# LSM6DS3_Breakout.net
KiCad netlist of a schematic drawn in EAGLE
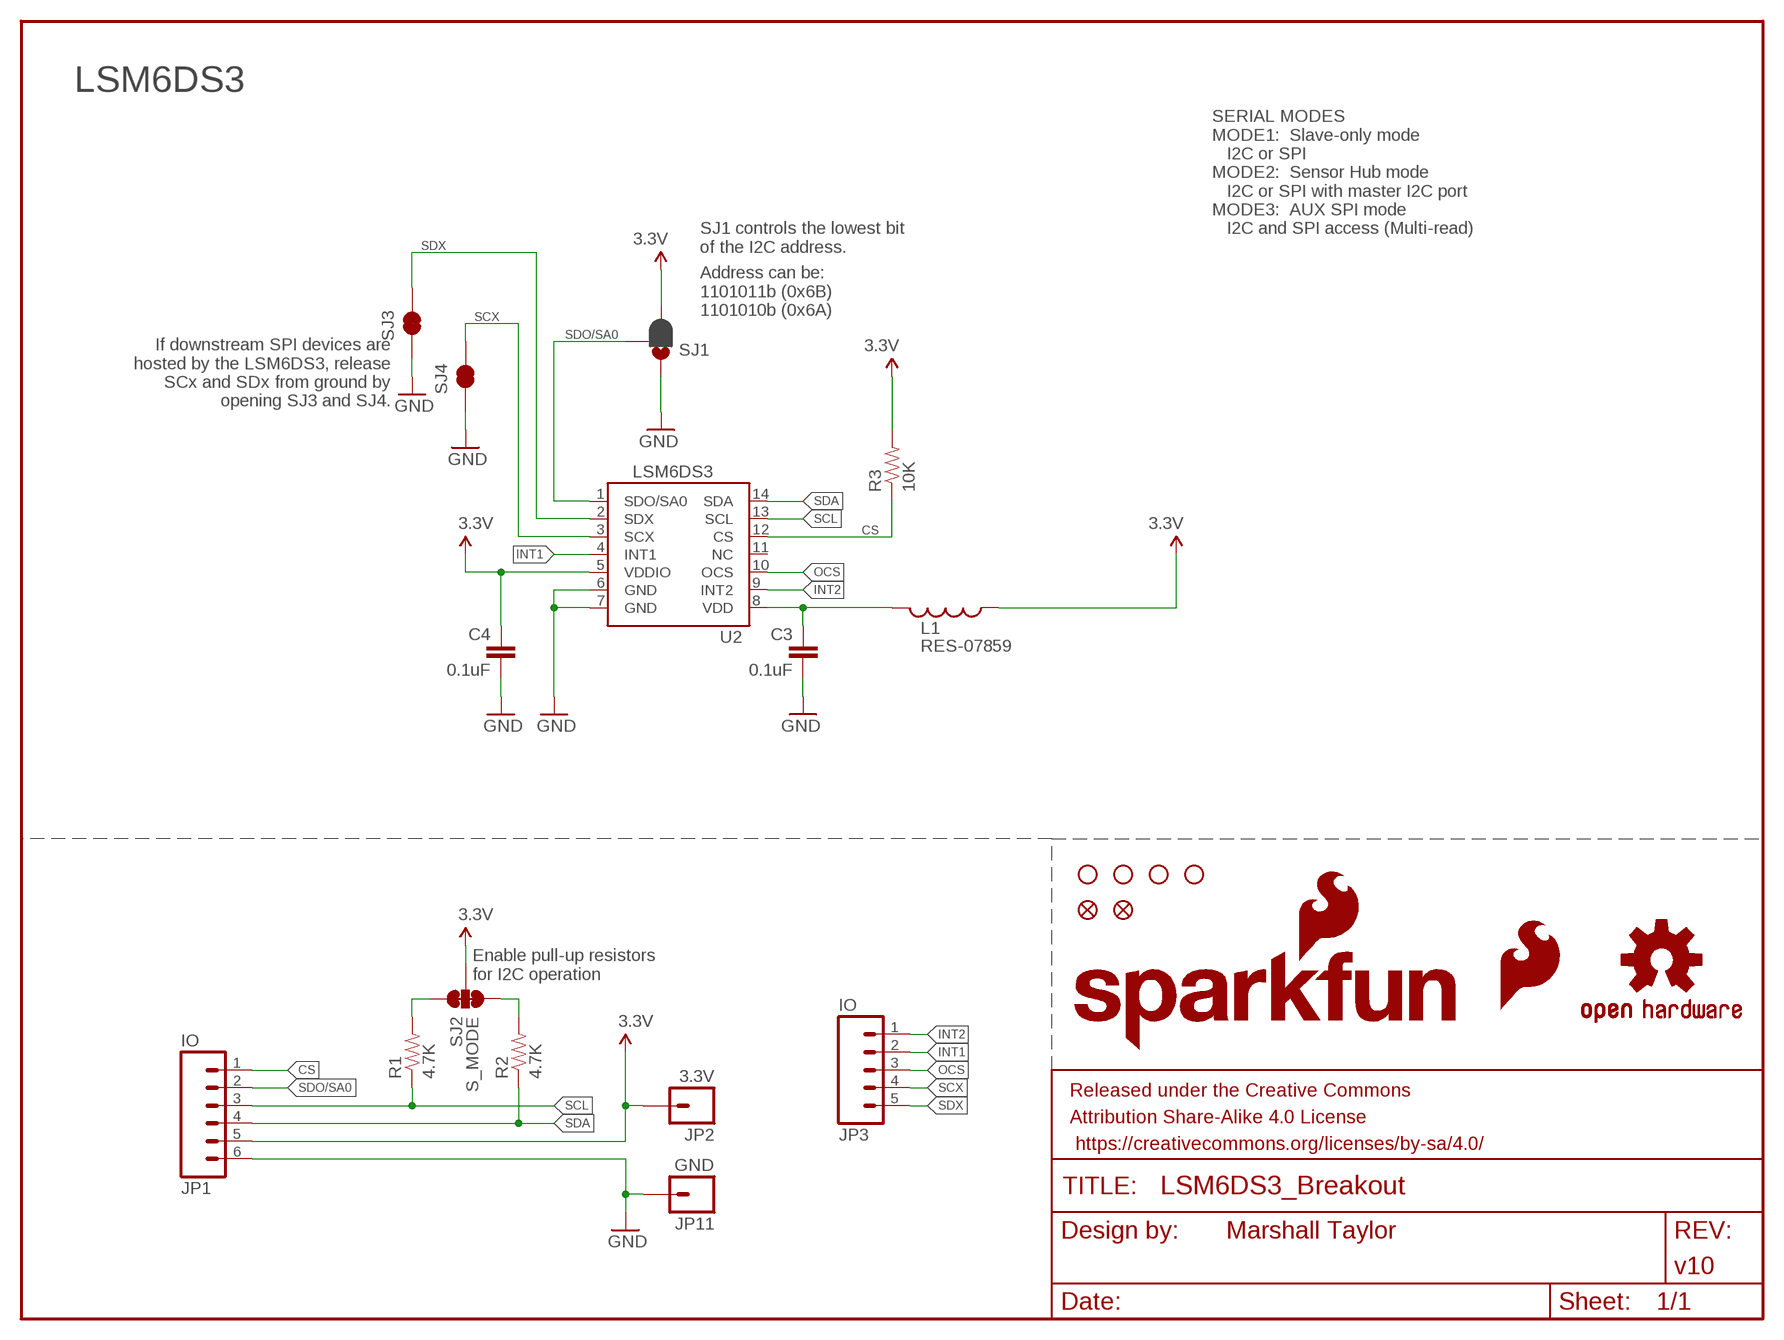
[diagram p0: schematic, sheet 1]

(export (version "E")
  (design (tool "Eeschema 10.0.6"))
  (components
    (comp (ref "C3")
      (value "0.1uF")
      (footprint "eagle-import:0603-CAP")
      (libsource (lib "eagle-import") (part "0.1UF-100V-10%(0603)"))
    )
    (comp (ref "C4")
      (value "0.1uF")
      (footprint "eagle-import:0603-CAP")
      (libsource (lib "eagle-import") (part "0.1UF-100V-10%(0603)"))
    )
    (comp (ref "FID1")
      (value "FIDUCIAL1X2")
      (footprint "eagle-import:FIDUCIAL-1X2")
      (libsource (lib "eagle-import") (part "FIDUCIAL1X2"))
    )
    (comp (ref "FID2")
      (value "FIDUCIAL1X2")
      (footprint "eagle-import:FIDUCIAL-1X2")
      (libsource (lib "eagle-import") (part "FIDUCIAL1X2"))
    )
    (comp (ref "FRAME1")
      (value "FRAME-LETTER")
      (footprint "eagle-import:CREATIVE_COMMONS")
      (fields
        (field (name "DESIGNER") "Marshall Taylor")
        (field (name "VERSION") "v10")
        (field (name "DESIGNER_1") "Marshall Taylor")
        (field (name "VERSION_1") "v10")
      )
      (libsource (lib "eagle-import") (part "FRAME-LETTER"))
    )
    (comp (ref "JP1")
      (value "IO")
      (footprint "eagle-import:1X06_NO_SILK_YES_STOP")
      (libsource (lib "eagle-import") (part "M06NO_SILK_YES_STOP"))
    )
    (comp (ref "JP2")
      (value "3.3V")
      (footprint "eagle-import:1X01_NO_SILK")
      (libsource (lib "eagle-import") (part "M01PTH_NO_SILK_YES_STOP"))
    )
    (comp (ref "JP3")
      (value "IO")
      (footprint "eagle-import:1X05")
      (libsource (lib "eagle-import") (part "M05PTH"))
    )
    (comp (ref "JP11")
      (value "GND")
      (footprint "eagle-import:1X01_NO_SILK")
      (libsource (lib "eagle-import") (part "M01PTH_NO_SILK_YES_STOP"))
    )
    (comp (ref "L1")
      (value "RES-07859")
      (footprint "eagle-import:0603")
      (libsource (lib "eagle-import") (part "INDUCTOR30OHM,1.8A"))
    )
    (comp (ref "LOGO1")
      (value "SFE_LOGO_FLAME.2_INCH")
      (footprint "eagle-import:SFE_LOGO_FLAME_.2")
      (libsource (lib "eagle-import") (part "SFE_LOGO_FLAME.2_INCH"))
    )
    (comp (ref "LOGO2")
      (value "OSHW-LOGOS")
      (footprint "eagle-import:OSHW-LOGO-S")
      (libsource (lib "eagle-import") (part "OSHW-LOGOS"))
    )
    (comp (ref "LOGO3")
      (value "SFE_LOGO_NAME_FLAME.1_INCH")
      (footprint "eagle-import:SFE_LOGO_NAME_FLAME_.1")
      (libsource (lib "eagle-import") (part "SFE_LOGO_NAME_FLAME.1_INCH"))
    )
    (comp (ref "R1")
      (value "4.7K")
      (footprint "eagle-import:0603-RES")
      (libsource (lib "eagle-import") (part "4.7KOHM-1/10W-1%(0603)"))
    )
    (comp (ref "R2")
      (value "4.7K")
      (footprint "eagle-import:0603-RES")
      (libsource (lib "eagle-import") (part "4.7KOHM-1/10W-1%(0603)"))
    )
    (comp (ref "R3")
      (value "10K")
      (footprint "eagle-import:0603-RES")
      (libsource (lib "eagle-import") (part "10KOHM-1/10W-1%(0603)0603"))
    )
    (comp (ref "SJ1")
      (value "JUMPER-PAD-3-2OF3_NC_BY_PASTE")
      (footprint "eagle-import:PAD-JUMPER-3-2OF3_NC_BY_PASTE_YES_SILK_FULL_BOX")
      (libsource (lib "eagle-import") (part "JUMPER-PAD-3-2OF3_NC_BY_PASTE"))
    )
    (comp (ref "SJ2")
      (value "S_MODE")
      (footprint "eagle-import:PAD-JUMPER-3-3OF3_NC_BY_TRACE_YES_SILK_FULL_BOX")
      (libsource (lib "eagle-import") (part "JUMPER-PAD-3-NC_BY_TRACE"))
    )
    (comp (ref "SJ3")
      (value "JUMPER-PAD-2-NC_BY_TRACE")
      (footprint "eagle-import:PAD-JUMPER-2-NC_BY_TRACE_YES_SILK")
      (libsource (lib "eagle-import") (part "JUMPER-PAD-2-NC_BY_TRACE"))
    )
    (comp (ref "SJ4")
      (value "JUMPER-PAD-2-NC_BY_TRACE")
      (footprint "eagle-import:PAD-JUMPER-2-NC_BY_TRACE_YES_SILK")
      (libsource (lib "eagle-import") (part "JUMPER-PAD-2-NC_BY_TRACE"))
    )
    (comp (ref "STANDOFF1")
      (value "STAND-OFF")
      (footprint "eagle-import:STAND-OFF")
      (libsource (lib "eagle-import") (part "STAND-OFF"))
    )
    (comp (ref "STANDOFF2")
      (value "STAND-OFF")
      (footprint "eagle-import:STAND-OFF")
      (libsource (lib "eagle-import") (part "STAND-OFF"))
    )
    (comp (ref "STANDOFF3")
      (value "STAND-OFF")
      (footprint "eagle-import:STAND-OFF")
      (libsource (lib "eagle-import") (part "STAND-OFF"))
    )
    (comp (ref "STANDOFF4")
      (value "STAND-OFF")
      (footprint "eagle-import:STAND-OFF")
      (libsource (lib "eagle-import") (part "STAND-OFF"))
    )
    (comp (ref "U2")
      (value "LSM6DS3")
      (footprint "eagle-import:LGA14L_DOT_INDICATOR")
      (libsource (lib "eagle-import") (part "LSM6DS3DOT_INDICATION"))
    )
  )
  (nets
    (net (code "1") (name "3.3V") (class "Default")
      (node (ref "C4") (pin "1") (pinfunction "1_1") (pintype "passive"))
      (node (ref "JP1") (pin "5") (pinfunction "5_5") (pintype "passive"))
      (node (ref "JP2") (pin "1") (pinfunction "1_1") (pintype "passive"))
      (node (ref "L1") (pin "1") (pinfunction "1_1") (pintype "passive"))
      (node (ref "R3") (pin "2") (pinfunction "2_2") (pintype "passive"))
      (node (ref "SJ1") (pin "3") (pinfunction "3_3") (pintype "passive"))
      (node (ref "SJ2") (pin "2") (pinfunction "2_2") (pintype "passive"))
      (node (ref "U2") (pin "5") (pinfunction "VDDIO_5") (pintype "bidirectional"))
    )
    (net (code "2") (name "CS") (class "Default")
      (node (ref "JP1") (pin "1") (pinfunction "1_1") (pintype "passive"))
      (node (ref "R3") (pin "1") (pinfunction "1_1") (pintype "passive"))
      (node (ref "U2") (pin "12") (pinfunction "CS_12") (pintype "bidirectional"))
    )
    (net (code "3") (name "GND") (class "Default")
      (node (ref "C3") (pin "2") (pinfunction "2_2") (pintype "passive"))
      (node (ref "C4") (pin "2") (pinfunction "2_2") (pintype "passive"))
      (node (ref "JP1") (pin "6") (pinfunction "6_6") (pintype "passive"))
      (node (ref "JP11") (pin "1") (pinfunction "1_1") (pintype "passive"))
      (node (ref "SJ1") (pin "1") (pinfunction "1_1") (pintype "passive"))
      (node (ref "SJ3") (pin "1") (pinfunction "1_1") (pintype "passive"))
      (node (ref "SJ4") (pin "1") (pinfunction "1_1") (pintype "passive"))
      (node (ref "U2") (pin "6") (pinfunction "GND_6") (pintype "bidirectional"))
      (node (ref "U2") (pin "7") (pinfunction "GND_7") (pintype "bidirectional"))
    )
    (net (code "4") (name "INT1") (class "Default")
      (node (ref "JP3") (pin "2") (pinfunction "2_2") (pintype "passive"))
      (node (ref "U2") (pin "4") (pinfunction "INT1_4") (pintype "bidirectional"))
    )
    (net (code "5") (name "INT2") (class "Default")
      (node (ref "JP3") (pin "1") (pinfunction "1_1") (pintype "passive"))
      (node (ref "U2") (pin "9") (pinfunction "INT2_9") (pintype "bidirectional"))
    )
    (net (code "6") (name "Net-(R1-Pad2)") (class "Default")
      (node (ref "R1") (pin "2") (pinfunction "2_2") (pintype "passive"))
      (node (ref "SJ2") (pin "1") (pinfunction "1_1") (pintype "passive"))
    )
    (net (code "7") (name "Net-(R2-Pad2)") (class "Default")
      (node (ref "R2") (pin "2") (pinfunction "2_2") (pintype "passive"))
      (node (ref "SJ2") (pin "3") (pinfunction "3_3") (pintype "passive"))
    )
    (net (code "8") (name "Net-(U2-VDD)") (class "Default")
      (node (ref "C3") (pin "1") (pinfunction "1_1") (pintype "passive"))
      (node (ref "L1") (pin "2") (pinfunction "2_2") (pintype "passive"))
      (node (ref "U2") (pin "8") (pinfunction "VDD_8") (pintype "bidirectional"))
    )
    (net (code "9") (name "OCS") (class "Default")
      (node (ref "JP3") (pin "3") (pinfunction "3_3") (pintype "passive"))
      (node (ref "U2") (pin "10") (pinfunction "OCS_10") (pintype "bidirectional"))
    )
    (net (code "10") (name "SCL") (class "Default")
      (node (ref "JP1") (pin "3") (pinfunction "3_3") (pintype "passive"))
      (node (ref "R1") (pin "1") (pinfunction "1_1") (pintype "passive"))
      (node (ref "U2") (pin "13") (pinfunction "SCL_13") (pintype "bidirectional"))
    )
    (net (code "11") (name "SCX") (class "Default")
      (node (ref "JP3") (pin "4") (pinfunction "4_4") (pintype "passive"))
      (node (ref "SJ4") (pin "2") (pinfunction "2_2") (pintype "passive"))
      (node (ref "U2") (pin "3") (pinfunction "SCX_3") (pintype "bidirectional"))
    )
    (net (code "12") (name "SDA") (class "Default")
      (node (ref "JP1") (pin "4") (pinfunction "4_4") (pintype "passive"))
      (node (ref "R2") (pin "1") (pinfunction "1_1") (pintype "passive"))
      (node (ref "U2") (pin "14") (pinfunction "SDA_14") (pintype "bidirectional"))
    )
    (net (code "13") (name "SDO{slash}SA0") (class "Default")
      (node (ref "JP1") (pin "2") (pinfunction "2_2") (pintype "passive"))
      (node (ref "SJ1") (pin "2") (pinfunction "2_2") (pintype "passive"))
      (node (ref "U2") (pin "1") (pinfunction "SDO/SA0_1") (pintype "bidirectional"))
    )
    (net (code "14") (name "SDX") (class "Default")
      (node (ref "JP3") (pin "5") (pinfunction "5_5") (pintype "passive"))
      (node (ref "SJ3") (pin "2") (pinfunction "2_2") (pintype "passive"))
      (node (ref "U2") (pin "2") (pinfunction "SDX_2") (pintype "bidirectional"))
    )
    (net (code "15") (name "unconnected-(U2-NC-Pad11)") (class "Default")
      (node (ref "U2") (pin "11") (pinfunction "NC_11") (pintype "bidirectional"))
    )
  )
)
